# UKU100.net
KiCad netlist of a schematic drawn in Altium Designer
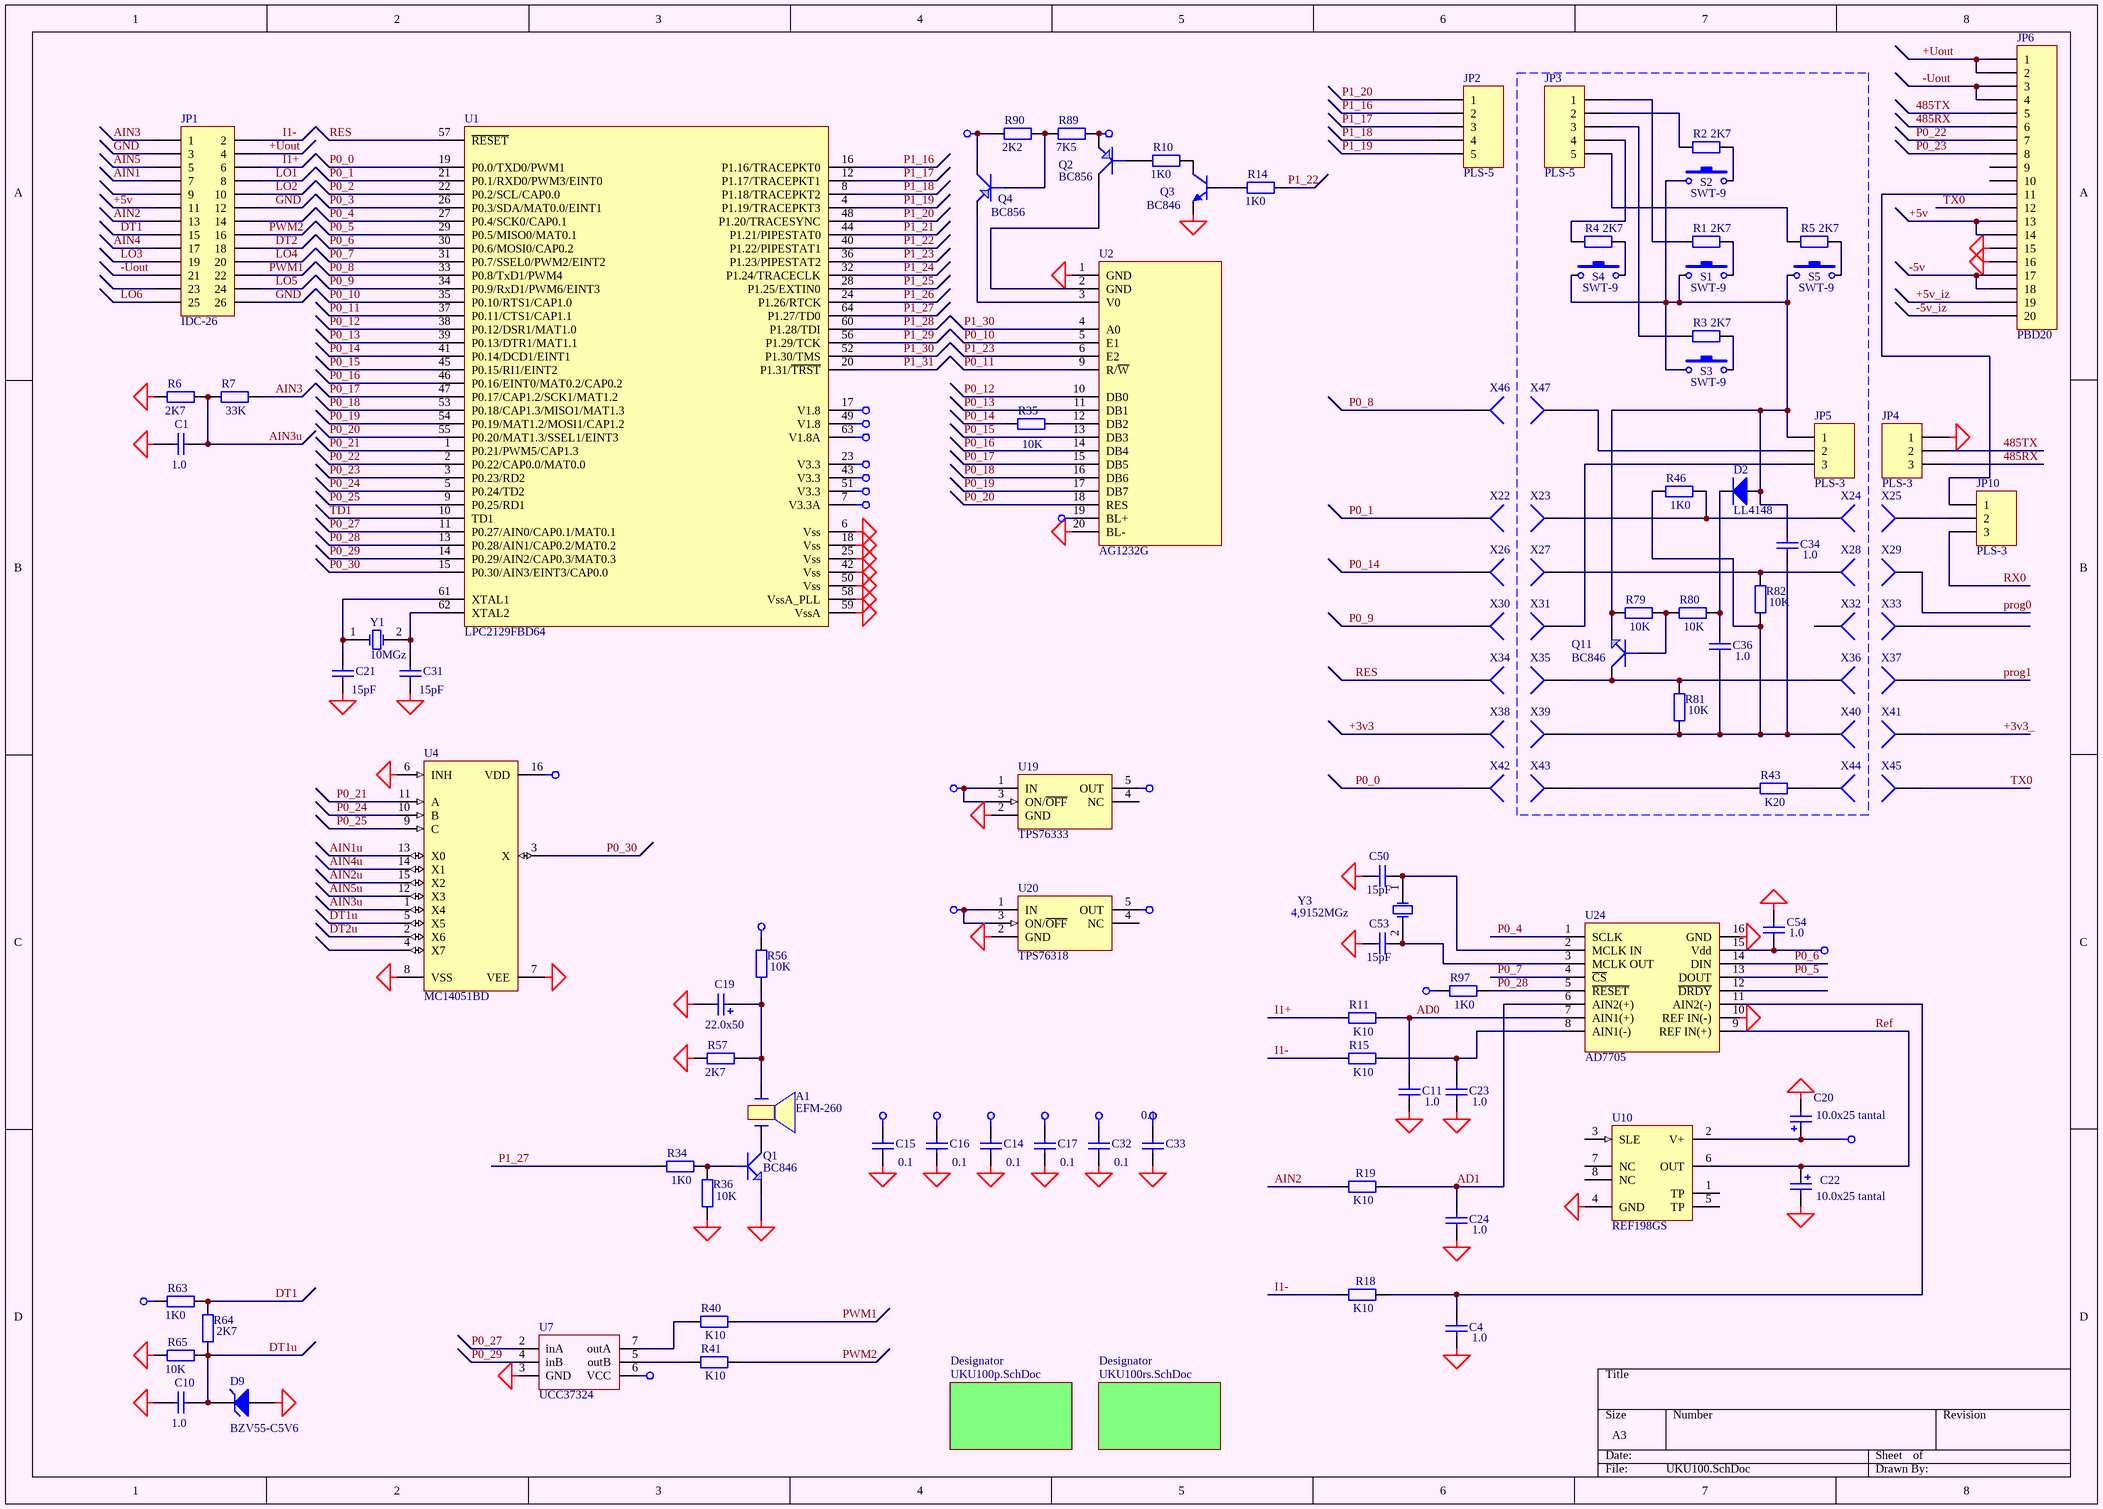
[diagram p0: UKU100.SchDoc]

(export (version "E")
  (design (tool "Eeschema 10.0.6"))
  (components
    (comp (ref "A1") (value "EFM-260") (footprint "Pjezo15") (libsource (lib "PAL") (part "PJEZ0")))
    (comp (ref "C1")
      (value "1.0")
      (footprint "C3216-1206")
      (description "Capacitor (Semiconductor SIM Model)")
      (fields (field (name "MANUFACTURER") "Generic Components") (field (name "PUBLISHER") "Altium Limited"))
      (libsource (lib "Miscellaneous Devices") (part "Cap Semi"))
    )
    (comp (ref "C4")
      (value "1.0")
      (footprint "_1206")
      (description "Capacitor (Semiconductor SIM Model)")
      (fields (field (name "MANUFACTURER") "Generic Components") (field (name "PUBLISHER") "Altium Limited"))
      (libsource (lib "Miscellaneous Devices") (part "Cap Semi"))
    )
    (comp (ref "C10")
      (value "1.0")
      (footprint "C3216-1206")
      (description "Capacitor (Semiconductor SIM Model)")
      (fields (field (name "MANUFACTURER") "Generic Components") (field (name "PUBLISHER") "Altium Limited"))
      (libsource (lib "Miscellaneous Devices") (part "Cap Semi"))
    )
    (comp (ref "C11")
      (value "1.0")
      (footprint "C3216-1206")
      (description "Capacitor (Semiconductor SIM Model)")
      (fields (field (name "MANUFACTURER") "Generic Components") (field (name "PUBLISHER") "Altium Limited"))
      (libsource (lib "Miscellaneous Devices") (part "Cap Semi"))
    )
    (comp (ref "C14")
      (value "0.1")
      (footprint "C3216-1206")
      (description "Capacitor (Semiconductor SIM Model)")
      (fields (field (name "MANUFACTURER") "Generic Components") (field (name "PUBLISHER") "Altium Limited"))
      (libsource (lib "Miscellaneous Devices") (part "Cap Semi"))
    )
    (comp (ref "C15")
      (value "0.1")
      (footprint "C3216-1206")
      (description "Capacitor (Semiconductor SIM Model)")
      (fields (field (name "MANUFACTURER") "Generic Components") (field (name "PUBLISHER") "Altium Limited"))
      (libsource (lib "Miscellaneous Devices") (part "Cap Semi"))
    )
    (comp (ref "C16")
      (value "0.1")
      (footprint "C3216-1206")
      (description "Capacitor (Semiconductor SIM Model)")
      (fields (field (name "MANUFACTURER") "Generic Components") (field (name "PUBLISHER") "Altium Limited"))
      (libsource (lib "Miscellaneous Devices") (part "Cap Semi"))
    )
    (comp (ref "C17")
      (value "0.1")
      (footprint "C3216-1206")
      (description "Capacitor (Semiconductor SIM Model)")
      (fields (field (name "MANUFACTURER") "Generic Components") (field (name "PUBLISHER") "Altium Limited"))
      (libsource (lib "Miscellaneous Devices") (part "Cap Semi"))
    )
    (comp (ref "C19")
      (value "22.0x50")
      (footprint "el3")
      (description "Polarized Capacitor (Radial)")
      (fields (field (name "MANUFACTURER") "Generic Components") (field (name "PUBLISHER") "Altium Limited"))
      (libsource (lib "PAL") (part "Cap Pol1"))
    )
    (comp (ref "C20")
      (value "10.0x25 tantal")
      (footprint "cap_el_6_3")
      (description "Polarized Capacitor (Surface Mount)")
      (fields (field (name "MANUFACTURER") "Generic Components") (field (name "PUBLISHER") "Altium Limited"))
      (libsource (lib "Miscellaneous Devices") (part "Cap Pol3"))
    )
    (comp (ref "C21")
      (value "15pF")
      (footprint "C3216-1206")
      (description "Capacitor (Semiconductor SIM Model)")
      (fields (field (name "MANUFACTURER") "Generic Components") (field (name "PUBLISHER") "Altium Limited"))
      (libsource (lib "Miscellaneous Devices") (part "Cap Semi"))
    )
    (comp (ref "C22")
      (value "10.0x25 tantal")
      (footprint "cap_el_6_3")
      (description "Polarized Capacitor (Surface Mount)")
      (fields (field (name "MANUFACTURER") "Generic Components") (field (name "PUBLISHER") "Altium Limited"))
      (libsource (lib "Miscellaneous Devices") (part "Cap Pol3"))
    )
    (comp (ref "C23")
      (value "1.0")
      (footprint "C3216-1206")
      (description "Capacitor (Semiconductor SIM Model)")
      (fields (field (name "MANUFACTURER") "Generic Components") (field (name "PUBLISHER") "Altium Limited"))
      (libsource (lib "Miscellaneous Devices") (part "Cap Semi"))
    )
    (comp (ref "C24")
      (value "1.0")
      (footprint "C3216-1206")
      (description "Capacitor (Semiconductor SIM Model)")
      (fields (field (name "MANUFACTURER") "Generic Components") (field (name "PUBLISHER") "Altium Limited"))
      (libsource (lib "Miscellaneous Devices") (part "Cap Semi"))
    )
    (comp (ref "C31")
      (value "15pF")
      (footprint "C3216-1206")
      (description "Capacitor (Semiconductor SIM Model)")
      (fields (field (name "MANUFACTURER") "Generic Components") (field (name "PUBLISHER") "Altium Limited"))
      (libsource (lib "Miscellaneous Devices") (part "Cap Semi"))
    )
    (comp (ref "C32")
      (value "0.1")
      (footprint "C3216-1206")
      (description "Capacitor (Semiconductor SIM Model)")
      (fields (field (name "MANUFACTURER") "Generic Components") (field (name "PUBLISHER") "Altium Limited"))
      (libsource (lib "Miscellaneous Devices") (part "Cap Semi"))
    )
    (comp (ref "C33")
      (value "0.1")
      (footprint "C3216-1206")
      (description "Capacitor (Semiconductor SIM Model)")
      (fields (field (name "MANUFACTURER") "Generic Components") (field (name "PUBLISHER") "Altium Limited"))
      (libsource (lib "Miscellaneous Devices") (part "Cap Semi"))
    )
    (comp (ref "C34")
      (value "1.0")
      (footprint "C3216-1206")
      (description "Capacitor (Semiconductor SIM Model)")
      (fields (field (name "MANUFACTURER") "Generic Components") (field (name "PUBLISHER") "Altium Limited"))
      (libsource (lib "Miscellaneous Devices") (part "Cap Semi"))
    )
    (comp (ref "C36")
      (value "1.0")
      (footprint "C3216-1206")
      (description "Capacitor (Semiconductor SIM Model)")
      (fields (field (name "MANUFACTURER") "Generic Components") (field (name "PUBLISHER") "Altium Limited"))
      (libsource (lib "Miscellaneous Devices") (part "Cap Semi"))
    )
    (comp (ref "C50")
      (value "15pF")
      (footprint "_1206")
      (description "Capacitor")
      (fields (field (name "MANUFACTURER") "Generic Components") (field (name "PUBLISHER") "Altium Limited"))
      (libsource (lib "") (part "Cap Semi_1"))
    )
    (comp (ref "C53")
      (value "15pF")
      (footprint "_1206")
      (description "Capacitor")
      (fields (field (name "MANUFACTURER") "Generic Components") (field (name "PUBLISHER") "Altium Limited"))
      (libsource (lib "") (part "Cap Semi_1"))
    )
    (comp (ref "C54")
      (value "1.0")
      (footprint "C3216-1206")
      (description "Capacitor")
      (fields (field (name "MANUFACTURER") "Generic Components") (field (name "PUBLISHER") "Altium Limited"))
      (libsource (lib "Miscellaneous Devices") (part "Cap Semi"))
    )
    (comp (ref "D2")
      (value "LL4148")
      (footprint "_1206d")
      (description "Default Diode")
      (fields (field (name "MANUFACTURER") "Generic Components") (field (name "PUBLISHER") "Altium Limited"))
      (libsource (lib "PAL") (part "Diode"))
    )
    (comp (ref "D9")
      (value "BZV55-C5V6")
      (footprint "_1206d")
      (description "Zener Diode")
      (fields (field (name "MANUFACTURER") "Generic Components") (field (name "PUBLISHER") "Altium Limited"))
      (libsource (lib "Miscellaneous Devices") (part "D Zener"))
    )
    (comp (ref "JP1")
      (value "IDC-26")
      (footprint "SCM-26")
      (description "Header, 13-Pin, Dual row")
      (fields (field (name "MANUFACTURER") "Generic Components") (field (name "PUBLISHER") "Altium Limited"))
      (libsource (lib "Miscellaneous Connectors") (part "MHDR2X13"))
    )
    (comp (ref "JP2")
      (value "PLS-5")
      (footprint "HDR1X5")
      (description "Header, 5-Pin")
      (fields (field (name "MANUFACTURER") "Generic Components") (field (name "PUBLISHER") "Altium Limited"))
      (libsource (lib "Miscellaneous Connectors") (part "Header 5"))
    )
    (comp (ref "JP3")
      (value "PLS-5")
      (footprint "HDR1X5")
      (description "Header, 5-Pin")
      (fields (field (name "MANUFACTURER") "Generic Components") (field (name "PUBLISHER") "Altium Limited"))
      (libsource (lib "") (part "Header 5_1"))
    )
    (comp (ref "JP4")
      (value "PLS-3")
      (footprint "HDR1X3")
      (description "Header, 3-Pin")
      (fields (field (name "MANUFACTURER") "Generic Components") (field (name "PUBLISHER") "Altium Limited"))
      (libsource (lib "") (part "Header 3_1"))
    )
    (comp (ref "JP5")
      (value "PLS-3")
      (footprint "HDR1X3")
      (description "Header, 3-Pin")
      (fields (field (name "MANUFACTURER") "Generic Components") (field (name "PUBLISHER") "Altium Limited"))
      (libsource (lib "Miscellaneous Connectors") (part "Header 3"))
    )
    (comp (ref "JP6")
      (value "PBD20")
      (footprint "HDR2X10")
      (description "Header, 20-Pin")
      (fields (field (name "MANUFACTURER") "Generic Components") (field (name "PUBLISHER") "Altium Limited"))
      (libsource (lib "Miscellaneous Connectors") (part "Header 20"))
    )
    (comp (ref "JP10")
      (value "PLS-3")
      (footprint "HDR1X3")
      (description "Header, 3-Pin")
      (fields (field (name "MANUFACTURER") "Generic Components") (field (name "PUBLISHER") "Altium Limited"))
      (libsource (lib "Miscellaneous Connectors") (part "Header 3"))
    )
    (comp (ref "Q1") (value "BC846") (footprint "SOT 23:SO-G3") (libsource (lib "MAIN") (part "GT122")))
    (comp (ref "Q2") (value "BC856") (footprint "SO-G3") (libsource (lib "MAIN") (part "GT109")))
    (comp (ref "Q3")
      (value "BC846")
      (footprint "SO-G3")
      (description "General Purpose Transistor NPN Silicon")
      (fields (field (name "MANUFACTURER") "Motorola") (field (name "PUBLISHER") "Altium Limited"))
      (libsource (lib "PAL") (part "BC847ALT1"))
    )
    (comp (ref "Q4") (value "BC856") (footprint "SO-G3") (libsource (lib "MAIN") (part "GT109")))
    (comp (ref "Q11") (value "BC846") (footprint "SOT 23:SO-G3") (libsource (lib "MAIN") (part "GT122")))
    (comp (ref "R1")
      (value "2K7")
      (footprint "_1206")
      (description "Resistor")
      (fields (field (name "MANUFACTURER") "Generic Components") (field (name "PUBLISHER") "Altium Limited"))
      (libsource (lib "") (part "Res2_3"))
    )
    (comp (ref "R2")
      (value "2K7")
      (footprint "_1206")
      (description "Resistor")
      (fields (field (name "MANUFACTURER") "Generic Components") (field (name "PUBLISHER") "Altium Limited"))
      (libsource (lib "") (part "Res2_3"))
    )
    (comp (ref "R3")
      (value "2K7")
      (footprint "_1206")
      (description "Resistor")
      (fields (field (name "MANUFACTURER") "Generic Components") (field (name "PUBLISHER") "Altium Limited"))
      (libsource (lib "") (part "Res2_3"))
    )
    (comp (ref "R4")
      (value "2K7")
      (footprint "_1206")
      (description "Resistor")
      (fields (field (name "MANUFACTURER") "Generic Components") (field (name "PUBLISHER") "Altium Limited"))
      (libsource (lib "") (part "Res2_3"))
    )
    (comp (ref "R5")
      (value "2K7")
      (footprint "_1206")
      (description "Resistor")
      (fields (field (name "MANUFACTURER") "Generic Components") (field (name "PUBLISHER") "Altium Limited"))
      (libsource (lib "") (part "Res2_3"))
    )
    (comp (ref "R6")
      (value "2K7")
      (footprint "_1206")
      (description "Resistor")
      (fields (field (name "MANUFACTURER") "Generic Components") (field (name "PUBLISHER") "Altium Limited"))
      (libsource (lib "") (part "Res2_1"))
    )
    (comp (ref "R7")
      (value "33K")
      (footprint "_1206")
      (description "Resistor")
      (fields (field (name "MANUFACTURER") "Generic Components") (field (name "PUBLISHER") "Altium Limited"))
      (libsource (lib "") (part "Res2_2"))
    )
    (comp (ref "R10")
      (value "1K0")
      (footprint "_1206")
      (description "Resistor")
      (fields (field (name "MANUFACTURER") "Generic Components") (field (name "PUBLISHER") "Altium Limited"))
      (libsource (lib "") (part "Res2_1"))
    )
    (comp (ref "R11")
      (value "K10")
      (footprint "_1206")
      (description "Resistor")
      (fields (field (name "MANUFACTURER") "Generic Components") (field (name "PUBLISHER") "Altium Limited"))
      (libsource (lib "") (part "Res2_1"))
    )
    (comp (ref "R14")
      (value "1K0")
      (footprint "_1206")
      (description "Resistor")
      (fields (field (name "MANUFACTURER") "Generic Components") (field (name "PUBLISHER") "Altium Limited"))
      (libsource (lib "") (part "Res2_1"))
    )
    (comp (ref "R15")
      (value "K10")
      (footprint "_1206")
      (description "Resistor")
      (fields (field (name "MANUFACTURER") "Generic Components") (field (name "PUBLISHER") "Altium Limited"))
      (libsource (lib "") (part "Res2_1"))
    )
    (comp (ref "R18")
      (value "K10")
      (footprint "_1206")
      (description "Resistor")
      (fields (field (name "MANUFACTURER") "Generic Components") (field (name "PUBLISHER") "Altium Limited"))
      (libsource (lib "") (part "Res2_1"))
    )
    (comp (ref "R19")
      (value "K10")
      (footprint "_1206")
      (description "Resistor")
      (fields (field (name "MANUFACTURER") "Generic Components") (field (name "PUBLISHER") "Altium Limited"))
      (libsource (lib "") (part "Res2_1"))
    )
    (comp (ref "R34")
      (value "1K0")
      (footprint "_1206")
      (description "Resistor")
      (fields (field (name "MANUFACTURER") "Generic Components") (field (name "PUBLISHER") "Altium Limited"))
      (libsource (lib "") (part "Res2_2"))
    )
    (comp (ref "R35")
      (value "10K")
      (footprint "_1206")
      (description "Resistor")
      (fields (field (name "MANUFACTURER") "Generic Components") (field (name "PUBLISHER") "Altium Limited"))
      (libsource (lib "") (part "Res2_2"))
    )
    (comp (ref "R36")
      (value "10K")
      (footprint "_1206")
      (description "Resistor")
      (fields (field (name "MANUFACTURER") "Generic Components") (field (name "PUBLISHER") "Altium Limited"))
      (libsource (lib "Miscellaneous Devices") (part "Res2"))
    )
    (comp (ref "R40")
      (value "K10")
      (footprint "_1206")
      (description "Resistor")
      (fields (field (name "MANUFACTURER") "Generic Components") (field (name "PUBLISHER") "Altium Limited"))
      (libsource (lib "") (part "Res2_1"))
    )
    (comp (ref "R41")
      (value "K10")
      (footprint "_1206")
      (description "Resistor")
      (fields (field (name "MANUFACTURER") "Generic Components") (field (name "PUBLISHER") "Altium Limited"))
      (libsource (lib "") (part "Res2_1"))
    )
    (comp (ref "R43")
      (value "K20")
      (footprint "_1206")
      (description "Resistor")
      (fields (field (name "MANUFACTURER") "Generic Components") (field (name "PUBLISHER") "Altium Limited"))
      (libsource (lib "") (part "Res2_2"))
    )
    (comp (ref "R46")
      (value "1K0")
      (footprint "_1206")
      (description "Resistor")
      (fields (field (name "MANUFACTURER") "Generic Components") (field (name "PUBLISHER") "Altium Limited"))
      (libsource (lib "") (part "Res2_1"))
    )
    (comp (ref "R56")
      (value "10K")
      (footprint "_1206")
      (description "Resistor")
      (fields (field (name "MANUFACTURER") "Generic Components") (field (name "PUBLISHER") "Altium Limited"))
      (libsource (lib "Miscellaneous Devices") (part "Res2"))
    )
    (comp (ref "R57")
      (value "2K7")
      (footprint "_1206")
      (description "Resistor")
      (fields (field (name "MANUFACTURER") "Generic Components") (field (name "PUBLISHER") "Altium Limited"))
      (libsource (lib "") (part "Res2_2"))
    )
    (comp (ref "R63")
      (value "1K0")
      (footprint "_1206")
      (description "Resistor")
      (fields (field (name "MANUFACTURER") "Generic Components") (field (name "PUBLISHER") "Altium Limited"))
      (libsource (lib "") (part "Res2_1"))
    )
    (comp (ref "R64")
      (value "2K7")
      (footprint "_1206")
      (description "Resistor")
      (fields (field (name "MANUFACTURER") "Generic Components") (field (name "PUBLISHER") "Altium Limited"))
      (libsource (lib "") (part "Res2_3"))
    )
    (comp (ref "R65")
      (value "10K")
      (footprint "_1206")
      (description "Resistor")
      (fields (field (name "MANUFACTURER") "Generic Components") (field (name "PUBLISHER") "Altium Limited"))
      (libsource (lib "") (part "Res2_2"))
    )
    (comp (ref "R79")
      (value "10K")
      (footprint "_1206")
      (description "Resistor")
      (fields (field (name "MANUFACTURER") "Generic Components") (field (name "PUBLISHER") "Altium Limited"))
      (libsource (lib "") (part "Res2_2"))
    )
    (comp (ref "R80")
      (value "10K")
      (footprint "_1206")
      (description "Resistor")
      (fields (field (name "MANUFACTURER") "Generic Components") (field (name "PUBLISHER") "Altium Limited"))
      (libsource (lib "") (part "Res2_2"))
    )
    (comp (ref "R81")
      (value "10K")
      (footprint "_1206")
      (description "Resistor")
      (fields (field (name "MANUFACTURER") "Generic Components") (field (name "PUBLISHER") "Altium Limited"))
      (libsource (lib "Miscellaneous Devices") (part "Res2"))
    )
    (comp (ref "R82")
      (value "10K")
      (footprint "_1206")
      (description "Resistor")
      (fields (field (name "MANUFACTURER") "Generic Components") (field (name "PUBLISHER") "Altium Limited"))
      (libsource (lib "Miscellaneous Devices") (part "Res2"))
    )
    (comp (ref "R89")
      (value "7K5")
      (footprint "_1206")
      (description "Resistor")
      (fields (field (name "MANUFACTURER") "Generic Components") (field (name "PUBLISHER") "Altium Limited"))
      (libsource (lib "") (part "Res2_2"))
    )
    (comp (ref "R90")
      (value "2K2")
      (footprint "_1206")
      (description "Resistor")
      (fields (field (name "MANUFACTURER") "Generic Components") (field (name "PUBLISHER") "Altium Limited"))
      (libsource (lib "") (part "Res2_2"))
    )
    (comp (ref "R97")
      (value "1K0")
      (footprint "_1206")
      (description "Resistor")
      (fields (field (name "MANUFACTURER") "Generic Components") (field (name "PUBLISHER") "Altium Limited"))
      (libsource (lib "") (part "Res2_1"))
    )
    (comp (ref "S1")
      (value "SWT-9")
      (footprint "SWT-9")
      (description "Switch")
      (fields (field (name "MANUFACTURER") "Generic Components") (field (name "PUBLISHER") "Altium Limited"))
      (libsource (lib "PAL") (part "SWT-9"))
    )
    (comp (ref "S2")
      (value "SWT-9")
      (footprint "SWT-9")
      (description "Switch")
      (fields (field (name "MANUFACTURER") "Generic Components") (field (name "PUBLISHER") "Altium Limited"))
      (libsource (lib "PAL") (part "SWT-9"))
    )
    (comp (ref "S3")
      (value "SWT-9")
      (footprint "SWT-9")
      (description "Switch")
      (fields (field (name "MANUFACTURER") "Generic Components") (field (name "PUBLISHER") "Altium Limited"))
      (libsource (lib "PAL") (part "SWT-9"))
    )
    (comp (ref "S4")
      (value "SWT-9")
      (footprint "SWT-9")
      (description "Switch")
      (fields (field (name "MANUFACTURER") "Generic Components") (field (name "PUBLISHER") "Altium Limited"))
      (libsource (lib "PAL") (part "SWT-9"))
    )
    (comp (ref "S5")
      (value "SWT-9")
      (footprint "SWT-9")
      (description "Switch")
      (fields (field (name "MANUFACTURER") "Generic Components") (field (name "PUBLISHER") "Altium Limited"))
      (libsource (lib "PAL") (part "SWT-9"))
    )
    (comp (ref "U1")
      (value "LPC2129FBD64")
      (footprint "F-QFP10X10-G64/P.5N")
      (libsource (lib "PAL") (part "LPC2129FBD64"))
    )
    (comp (ref "U2") (value "AG1232G") (footprint "AG1232G") (libsource (lib "PAL") (part "AG1232G")))
    (comp (ref "U4")
      (value "MC14051BD")
      (footprint "SO-G16/C5.85")
      (description "8-Channel Analog Multiplexer/Demultiplexer")
      (fields (field (name "MANUFACTURER") "ON Semiconductor") (field (name "PUBLISHER") "Altium Limited"))
      (libsource (lib "ON Semi Logic Multiplexer") (part "MC14051BD"))
    )
    (comp (ref "U7") (value "UCC37324") (footprint "SO-G8") (libsource (lib "PAL") (part "UCC37324")))
    (comp (ref "U10")
      (value "REF198GS")
      (footprint "SO-G8")
      (description "Precision Micropower, Low-Dropout, Voltage Reference")
      (fields (field (name "MANUFACTURER") "Analog Devices") (field (name "PUBLISHER") "Altium Limited"))
      (libsource (lib "AD Power Mgt Voltage Reference") (part "REF198GS"))
    )
    (comp (ref "U19")
      (value "TPS76333")
      (footprint "SO-G5/P.95")
      (description "Micropower SOT, 50 mA Ultra Low-Dropout Regulator")
      (fields
        (field (name "MANUFACTURER") "National Semiconductor")
        (field (name "PUBLISHER") "Altium Limited")
      )
      (libsource (lib "NSC Power Mgt Voltage Regulator") (part "LP2980AIM5-3.3"))
    )
    (comp (ref "U20")
      (value "TPS76318")
      (footprint "SO-G5/P.95")
      (description "Micropower SOT, 50 mA Ultra Low-Dropout Regulator")
      (fields
        (field (name "MANUFACTURER") "National Semiconductor")
        (field (name "PUBLISHER") "Altium Limited")
      )
      (libsource (lib "NSC Power Mgt Voltage Regulator") (part "LP2980AIM5-3.3"))
    )
    (comp (ref "U24")
      (value "AD7705")
      (footprint "SO-G16/D10.4")
      (description "ADC")
      (libsource (lib "PAL") (part "AD7705"))
    )
    (comp (ref "X22")
      (value "~")
      (footprint "PIN1")
      (description "Socket")
      (fields (field (name "MANUFACTURER") "Generic Components") (field (name "PUBLISHER") "Altium Limited"))
      (libsource (lib "Miscellaneous Connectors") (part "Socket"))
    )
    (comp (ref "X23")
      (value "~")
      (footprint "PIN1")
      (description "Socket")
      (fields (field (name "MANUFACTURER") "Generic Components") (field (name "PUBLISHER") "Altium Limited"))
      (libsource (lib "Miscellaneous Connectors") (part "Socket"))
    )
    (comp (ref "X24")
      (value "~")
      (footprint "PIN1")
      (description "Socket")
      (fields (field (name "MANUFACTURER") "Generic Components") (field (name "PUBLISHER") "Altium Limited"))
      (libsource (lib "Miscellaneous Connectors") (part "Socket"))
    )
    (comp (ref "X25")
      (value "~")
      (footprint "PIN1")
      (description "Socket")
      (fields (field (name "MANUFACTURER") "Generic Components") (field (name "PUBLISHER") "Altium Limited"))
      (libsource (lib "Miscellaneous Connectors") (part "Socket"))
    )
    (comp (ref "X26")
      (value "~")
      (footprint "PIN1")
      (description "Socket")
      (fields (field (name "MANUFACTURER") "Generic Components") (field (name "PUBLISHER") "Altium Limited"))
      (libsource (lib "Miscellaneous Connectors") (part "Socket"))
    )
    (comp (ref "X27")
      (value "~")
      (footprint "PIN1")
      (description "Socket")
      (fields (field (name "MANUFACTURER") "Generic Components") (field (name "PUBLISHER") "Altium Limited"))
      (libsource (lib "Miscellaneous Connectors") (part "Socket"))
    )
    (comp (ref "X28")
      (value "~")
      (footprint "PIN1")
      (description "Socket")
      (fields (field (name "MANUFACTURER") "Generic Components") (field (name "PUBLISHER") "Altium Limited"))
      (libsource (lib "Miscellaneous Connectors") (part "Socket"))
    )
    (comp (ref "X29")
      (value "~")
      (footprint "PIN1")
      (description "Socket")
      (fields (field (name "MANUFACTURER") "Generic Components") (field (name "PUBLISHER") "Altium Limited"))
      (libsource (lib "Miscellaneous Connectors") (part "Socket"))
    )
    (comp (ref "X30")
      (value "~")
      (footprint "PIN1")
      (description "Socket")
      (fields (field (name "MANUFACTURER") "Generic Components") (field (name "PUBLISHER") "Altium Limited"))
      (libsource (lib "Miscellaneous Connectors") (part "Socket"))
    )
    (comp (ref "X31")
      (value "~")
      (footprint "PIN1")
      (description "Socket")
      (fields (field (name "MANUFACTURER") "Generic Components") (field (name "PUBLISHER") "Altium Limited"))
      (libsource (lib "Miscellaneous Connectors") (part "Socket"))
    )
    (comp (ref "X32")
      (value "~")
      (footprint "PIN1")
      (description "Socket")
      (fields (field (name "MANUFACTURER") "Generic Components") (field (name "PUBLISHER") "Altium Limited"))
      (libsource (lib "Miscellaneous Connectors") (part "Socket"))
    )
    (comp (ref "X33")
      (value "~")
      (footprint "PIN1")
      (description "Socket")
      (fields (field (name "MANUFACTURER") "Generic Components") (field (name "PUBLISHER") "Altium Limited"))
      (libsource (lib "Miscellaneous Connectors") (part "Socket"))
    )
    (comp (ref "X34")
      (value "~")
      (footprint "PIN1")
      (description "Socket")
      (fields (field (name "MANUFACTURER") "Generic Components") (field (name "PUBLISHER") "Altium Limited"))
      (libsource (lib "Miscellaneous Connectors") (part "Socket"))
    )
    (comp (ref "X35")
      (value "~")
      (footprint "PIN1")
      (description "Socket")
      (fields (field (name "MANUFACTURER") "Generic Components") (field (name "PUBLISHER") "Altium Limited"))
      (libsource (lib "Miscellaneous Connectors") (part "Socket"))
    )
    (comp (ref "X36")
      (value "~")
      (footprint "PIN1")
      (description "Socket")
      (fields (field (name "MANUFACTURER") "Generic Components") (field (name "PUBLISHER") "Altium Limited"))
      (libsource (lib "Miscellaneous Connectors") (part "Socket"))
    )
    (comp (ref "X37")
      (value "~")
      (footprint "PIN1")
      (description "Socket")
      (fields (field (name "MANUFACTURER") "Generic Components") (field (name "PUBLISHER") "Altium Limited"))
      (libsource (lib "Miscellaneous Connectors") (part "Socket"))
    )
    (comp (ref "X38")
      (value "~")
      (footprint "PIN1")
      (description "Socket")
      (fields (field (name "MANUFACTURER") "Generic Components") (field (name "PUBLISHER") "Altium Limited"))
      (libsource (lib "Miscellaneous Connectors") (part "Socket"))
    )
    (comp (ref "X39")
      (value "~")
      (footprint "PIN1")
      (description "Socket")
      (fields (field (name "MANUFACTURER") "Generic Components") (field (name "PUBLISHER") "Altium Limited"))
      (libsource (lib "Miscellaneous Connectors") (part "Socket"))
    )
    (comp (ref "X40")
      (value "~")
      (footprint "PIN1")
      (description "Socket")
      (fields (field (name "MANUFACTURER") "Generic Components") (field (name "PUBLISHER") "Altium Limited"))
      (libsource (lib "Miscellaneous Connectors") (part "Socket"))
    )
    (comp (ref "X41")
      (value "~")
      (footprint "PIN1")
      (description "Socket")
      (fields (field (name "MANUFACTURER") "Generic Components") (field (name "PUBLISHER") "Altium Limited"))
      (libsource (lib "Miscellaneous Connectors") (part "Socket"))
    )
    (comp (ref "X42")
      (value "~")
      (footprint "PIN1")
      (description "Socket")
      (fields (field (name "MANUFACTURER") "Generic Components") (field (name "PUBLISHER") "Altium Limited"))
      (libsource (lib "Miscellaneous Connectors") (part "Socket"))
    )
    (comp (ref "X43")
      (value "~")
      (footprint "PIN1")
      (description "Socket")
      (fields (field (name "MANUFACTURER") "Generic Components") (field (name "PUBLISHER") "Altium Limited"))
      (libsource (lib "Miscellaneous Connectors") (part "Socket"))
    )
    (comp (ref "X44")
      (value "~")
      (footprint "PIN1")
      (description "Socket")
      (fields (field (name "MANUFACTURER") "Generic Components") (field (name "PUBLISHER") "Altium Limited"))
      (libsource (lib "Miscellaneous Connectors") (part "Socket"))
    )
    (comp (ref "X45")
      (value "~")
      (footprint "PIN1")
      (description "Socket")
      (fields (field (name "MANUFACTURER") "Generic Components") (field (name "PUBLISHER") "Altium Limited"))
      (libsource (lib "Miscellaneous Connectors") (part "Socket"))
    )
    (comp (ref "X46")
      (value "~")
      (footprint "PIN1")
      (description "Socket")
      (fields (field (name "MANUFACTURER") "Generic Components") (field (name "PUBLISHER") "Altium Limited"))
      (libsource (lib "Miscellaneous Connectors") (part "Socket"))
    )
    (comp (ref "X47")
      (value "~")
      (footprint "PIN1")
      (description "Socket")
      (fields (field (name "MANUFACTURER") "Generic Components") (field (name "PUBLISHER") "Altium Limited"))
      (libsource (lib "Miscellaneous Connectors") (part "Socket"))
    )
    (comp (ref "Y1")
      (value "10MGz")
      (footprint "QWARZ1")
      (description "Crystal Oscillator")
      (fields (field (name "MANUFACTURER") "Generic Components") (field (name "PUBLISHER") "Altium Limited"))
      (libsource (lib "") (part "XTAL_1"))
    )
    (comp (ref "Y3")
      (value "4,9152MGz")
      (footprint "QWARZ1")
      (description "Crystal Oscillator")
      (fields (field (name "MANUFACTURER") "Generic Components") (field (name "PUBLISHER") "Altium Limited"))
      (libsource (lib "Miscellaneous Devices") (part "XTAL"))
    )
  )
  (nets
    (net (code "1") (name "+1v8") (class "Default")
      (node (ref "C14") (pin "2") (pinfunction "2_2") (pintype "passive"))
      (node (ref "C32") (pin "2") (pinfunction "2_2") (pintype "passive"))
      (node (ref "U1") (pin "17") (pinfunction "V1.8_17") (pintype "passive"))
      (node (ref "U1") (pin "49") (pinfunction "V1.8_49") (pintype "passive"))
      (node (ref "U1") (pin "63") (pinfunction "V1.8A_63") (pintype "passive"))
      (node (ref "U20") (pin "5") (pinfunction "OUT_5") (pintype "power_in"))
    )
    (net (code "2") (name "+3v3") (class "Default")
      (node (ref "C33") (pin "2") (pinfunction "2_2") (pintype "passive"))
      (node (ref "U1") (pin "23") (pinfunction "V3.3_23") (pintype "passive"))
      (node (ref "U1") (pin "43") (pinfunction "V3.3_43") (pintype "passive"))
      (node (ref "U1") (pin "51") (pinfunction "V3.3_51") (pintype "passive"))
      (node (ref "U1") (pin "7") (pinfunction "V3.3A_7") (pintype "passive"))
      (node (ref "X38") (pin "1") (pinfunction "1_1") (pintype "passive"))
    )
    (net (code "3") (name "+3v3_") (class "Default")
      (node (ref "C17") (pin "2") (pinfunction "2_2") (pintype "passive"))
      (node (ref "U19") (pin "5") (pinfunction "OUT_5") (pintype "power_in"))
      (node (ref "X41") (pin "1") (pinfunction "1_1") (pintype "passive"))
    )
    (net (code "4") (name "+5v") (class "Default")
      (node (ref "C15") (pin "2") (pinfunction "2_2") (pintype "passive"))
      (node (ref "C20") (pin "1") (pinfunction "1_1") (pintype "passive"))
      (node (ref "C54") (pin "2") (pinfunction "2_2") (pintype "passive"))
      (node (ref "JP1") (pin "11") (pinfunction "11_11") (pintype "passive"))
      (node (ref "JP6") (pin "13") (pinfunction "13_13") (pintype "passive"))
      (node (ref "JP6") (pin "14") (pinfunction "14_14") (pintype "passive"))
      (node (ref "Q2") (pin "2") (pinfunction "E_2") (pintype "passive"))
      (node (ref "R63") (pin "2") (pinfunction "2_2") (pintype "passive"))
      (node (ref "R89") (pin "2") (pinfunction "2_2") (pintype "passive"))
      (node (ref "R97") (pin "2") (pinfunction "2_2") (pintype "passive"))
      (node (ref "U10") (pin "2") (pinfunction "V+_2") (pintype "power_in"))
      (node (ref "U19") (pin "1") (pinfunction "IN_1") (pintype "power_in"))
      (node (ref "U19") (pin "3") (pinfunction "ON/~{OFF}_3") (pintype "input"))
      (node (ref "U2") (pin "19") (pinfunction "BL+_19") (pintype "passive"))
      (node (ref "U20") (pin "1") (pinfunction "IN_1") (pintype "power_in"))
      (node (ref "U20") (pin "3") (pinfunction "ON/~{OFF}_3") (pintype "input"))
      (node (ref "U24") (pin "15") (pinfunction "Vdd_15") (pintype "passive"))
      (node (ref "U4") (pin "16") (pinfunction "VDD_16") (pintype "power_in"))
      (node (ref "U7") (pin "6") (pinfunction "VCC_6") (pintype "passive"))
    )
    (net (code "5") (name "+Uout") (class "Default")
      (node (ref "JP1") (pin "4") (pinfunction "4_4") (pintype "passive"))
      (node (ref "JP6") (pin "1") (pinfunction "1_1") (pintype "passive"))
      (node (ref "JP6") (pin "2") (pinfunction "2_2") (pintype "passive"))
      (node (ref "R56") (pin "2") (pinfunction "2_2") (pintype "passive"))
    )
    (net (code "6") (name "-5v") (class "Default")
      (node (ref "C16") (pin "2") (pinfunction "2_2") (pintype "passive"))
      (node (ref "JP6") (pin "17") (pinfunction "17_17") (pintype "passive"))
      (node (ref "JP6") (pin "18") (pinfunction "18_18") (pintype "passive"))
      (node (ref "Q4") (pin "3") (pinfunction "C_3") (pintype "passive"))
      (node (ref "R90") (pin "1") (pinfunction "1_1") (pintype "passive"))
    )
    (net (code "7") (name "/+5v_iz") (class "Default")
      (node (ref "JP6") (pin "19") (pinfunction "19_19") (pintype "passive"))
    )
    (net (code "8") (name "/-5v_iz") (class "Default")
      (node (ref "JP6") (pin "20") (pinfunction "20_20") (pintype "passive"))
    )
    (net (code "9") (name "/-Uout") (class "Default")
      (node (ref "JP1") (pin "21") (pinfunction "21_21") (pintype "passive"))
      (node (ref "JP6") (pin "3") (pinfunction "3_3") (pintype "passive"))
      (node (ref "JP6") (pin "4") (pinfunction "4_4") (pintype "passive"))
    )
    (net (code "10") (name "/485RX") (class "Default")
      (node (ref "JP4") (pin "3") (pinfunction "3_3") (pintype "passive"))
      (node (ref "JP6") (pin "6") (pinfunction "6_6") (pintype "passive"))
    )
    (net (code "11") (name "/485TX") (class "Default")
      (node (ref "JP4") (pin "2") (pinfunction "2_2") (pintype "passive"))
      (node (ref "JP6") (pin "5") (pinfunction "5_5") (pintype "passive"))
    )
    (net (code "12") (name "/AD0") (class "Default")
      (node (ref "C11") (pin "2") (pinfunction "2_2") (pintype "passive"))
      (node (ref "R11") (pin "1") (pinfunction "1_1") (pintype "passive"))
      (node (ref "U24") (pin "7") (pinfunction "AIN1(+)_7") (pintype "passive"))
    )
    (net (code "13") (name "/AD1") (class "Default")
      (node (ref "C24") (pin "2") (pinfunction "2_2") (pintype "passive"))
      (node (ref "R19") (pin "1") (pinfunction "1_1") (pintype "passive"))
      (node (ref "U24") (pin "6") (pinfunction "AIN2(+)_6") (pintype "passive"))
    )
    (net (code "14") (name "/AIN1") (class "Default")
      (node (ref "JP1") (pin "7") (pinfunction "7_7") (pintype "passive"))
    )
    (net (code "15") (name "/AIN1u") (class "Default")
      (node (ref "U4") (pin "13") (pinfunction "X0_13") (pintype "bidirectional"))
    )
    (net (code "16") (name "/AIN2") (class "Default")
      (node (ref "JP1") (pin "13") (pinfunction "13_13") (pintype "passive"))
      (node (ref "R19") (pin "2") (pinfunction "2_2") (pintype "passive"))
    )
    (net (code "17") (name "/AIN2u") (class "Default")
      (node (ref "U4") (pin "15") (pinfunction "X2_15") (pintype "bidirectional"))
    )
    (net (code "18") (name "/AIN3") (class "Default")
      (node (ref "JP1") (pin "1") (pinfunction "1_1") (pintype "passive"))
      (node (ref "R7") (pin "2") (pinfunction "2_2") (pintype "passive"))
    )
    (net (code "19") (name "/AIN3u") (class "Default")
      (node (ref "C1") (pin "1") (pinfunction "1_1") (pintype "passive"))
      (node (ref "R6") (pin "1") (pinfunction "1_1") (pintype "passive"))
      (node (ref "R7") (pin "1") (pinfunction "1_1") (pintype "passive"))
      (node (ref "U4") (pin "1") (pinfunction "X4_1") (pintype "bidirectional"))
    )
    (net (code "20") (name "/AIN4") (class "Default")
      (node (ref "JP1") (pin "17") (pinfunction "17_17") (pintype "passive"))
    )
    (net (code "21") (name "/AIN4u") (class "Default")
      (node (ref "U4") (pin "14") (pinfunction "X1_14") (pintype "bidirectional"))
    )
    (net (code "22") (name "/AIN5") (class "Default")
      (node (ref "JP1") (pin "5") (pinfunction "5_5") (pintype "passive"))
    )
    (net (code "23") (name "/AIN5u") (class "Default")
      (node (ref "U4") (pin "12") (pinfunction "X3_12") (pintype "bidirectional"))
    )
    (net (code "24") (name "/DT1") (class "Default")
      (node (ref "JP1") (pin "15") (pinfunction "15_15") (pintype "passive"))
      (node (ref "R63") (pin "1") (pinfunction "1_1") (pintype "passive"))
      (node (ref "R64") (pin "1") (pinfunction "1_1") (pintype "passive"))
    )
    (net (code "25") (name "/DT1u") (class "Default")
      (node (ref "C10") (pin "1") (pinfunction "1_1") (pintype "passive"))
      (node (ref "D9") (pin "2") (pinfunction "K_2") (pintype "passive"))
      (node (ref "R64") (pin "2") (pinfunction "2_2") (pintype "passive"))
      (node (ref "R65") (pin "2") (pinfunction "2_2") (pintype "passive"))
      (node (ref "U4") (pin "5") (pinfunction "X5_5") (pintype "bidirectional"))
    )
    (net (code "26") (name "/DT2") (class "Default")
      (node (ref "JP1") (pin "18") (pinfunction "18_18") (pintype "passive"))
    )
    (net (code "27") (name "/DT2u") (class "Default")
      (node (ref "U4") (pin "2") (pinfunction "X6_2") (pintype "bidirectional"))
    )
    (net (code "28") (name "/I1+") (class "Default")
      (node (ref "JP1") (pin "6") (pinfunction "6_6") (pintype "passive"))
      (node (ref "R11") (pin "2") (pinfunction "2_2") (pintype "passive"))
    )
    (net (code "29") (name "/I1-") (class "Default")
      (node (ref "JP1") (pin "2") (pinfunction "2_2") (pintype "passive"))
      (node (ref "R15") (pin "2") (pinfunction "2_2") (pintype "passive"))
      (node (ref "R18") (pin "2") (pinfunction "2_2") (pintype "passive"))
    )
    (net (code "30") (name "/LO1") (class "Default")
      (node (ref "JP1") (pin "8") (pinfunction "8_8") (pintype "passive"))
    )
    (net (code "31") (name "/LO2") (class "Default")
      (node (ref "JP1") (pin "10") (pinfunction "10_10") (pintype "passive"))
    )
    (net (code "32") (name "/LO3") (class "Default")
      (node (ref "JP1") (pin "19") (pinfunction "19_19") (pintype "passive"))
    )
    (net (code "33") (name "/LO4") (class "Default")
      (node (ref "JP1") (pin "20") (pinfunction "20_20") (pintype "passive"))
    )
    (net (code "34") (name "/LO5") (class "Default")
      (node (ref "JP1") (pin "24") (pinfunction "24_24") (pintype "passive"))
    )
    (net (code "35") (name "/LO6") (class "Default")
      (node (ref "JP1") (pin "25") (pinfunction "25_25") (pintype "passive"))
    )
    (net (code "36") (name "/P0_0") (class "Default")
      (node (ref "U1") (pin "19") (pinfunction "P0.0/TXD0/PWM1_19") (pintype "passive"))
      (node (ref "X42") (pin "1") (pinfunction "1_1") (pintype "passive"))
    )
    (net (code "37") (name "/P0_1") (class "Default")
      (node (ref "U1") (pin "21") (pinfunction "P0.1/RXD0/PWM3/EINT0_21") (pintype "passive"))
      (node (ref "X22") (pin "1") (pinfunction "1_1") (pintype "passive"))
    )
    (net (code "38") (name "/P0_2") (class "Default")
      (node (ref "U1") (pin "22") (pinfunction "P0.2/SCL/CAP0.0_22") (pintype "passive"))
    )
    (net (code "39") (name "/P0_3") (class "Default")
      (node (ref "U1") (pin "26") (pinfunction "P0.3/SDA/MAT0.0/EINT1_26") (pintype "passive"))
    )
    (net (code "40") (name "/P0_4") (class "Default")
      (node (ref "U1") (pin "27") (pinfunction "P0.4/SCK0/CAP0.1_27") (pintype "passive"))
      (node (ref "U24") (pin "1") (pinfunction "SCLK_1") (pintype "passive"))
    )
    (net (code "41") (name "/P0_5") (class "Default")
      (node (ref "U1") (pin "29") (pinfunction "P0.5/MISO0/MAT0.1_29") (pintype "passive"))
      (node (ref "U24") (pin "13") (pinfunction "DOUT_13") (pintype "passive"))
    )
    (net (code "42") (name "/P0_6") (class "Default")
      (node (ref "U1") (pin "30") (pinfunction "P0.6/MOSI0/CAP0.2_30") (pintype "passive"))
      (node (ref "U24") (pin "14") (pinfunction "DIN_14") (pintype "passive"))
    )
    (net (code "43") (name "/P0_7") (class "Default")
      (node (ref "U1") (pin "31") (pinfunction "P0.7/SSEL0/PWM2/EINT2_31") (pintype "passive"))
      (node (ref "U24") (pin "4") (pinfunction "~{CS}_4") (pintype "passive"))
    )
    (net (code "44") (name "/P0_8") (class "Default")
      (node (ref "U1") (pin "33") (pinfunction "P0.8/TxD1/PWM4_33") (pintype "passive"))
      (node (ref "X46") (pin "1") (pinfunction "1_1") (pintype "passive"))
    )
    (net (code "45") (name "/P0_9") (class "Default")
      (node (ref "U1") (pin "34") (pinfunction "P0.9/RxD1/PWM6/EINT3_34") (pintype "passive"))
      (node (ref "X30") (pin "1") (pinfunction "1_1") (pintype "passive"))
    )
    (net (code "46") (name "/P0_10") (class "Default")
      (node (ref "U1") (pin "35") (pinfunction "P0.10/RTS1/CAP1.0_35") (pintype "passive"))
      (node (ref "U2") (pin "5") (pinfunction "E1_5") (pintype "passive"))
    )
    (net (code "47") (name "/P0_11") (class "Default")
      (node (ref "U1") (pin "37") (pinfunction "P0.11/CTS1/CAP1.1_37") (pintype "passive"))
      (node (ref "U2") (pin "9") (pinfunction "R/~{W}_9") (pintype "passive"))
    )
    (net (code "48") (name "/P0_12") (class "Default")
      (node (ref "U1") (pin "38") (pinfunction "P0.12/DSR1/MAT1.0_38") (pintype "passive"))
      (node (ref "U2") (pin "10") (pinfunction "DB0_10") (pintype "passive"))
    )
    (net (code "49") (name "/P0_13") (class "Default")
      (node (ref "U1") (pin "39") (pinfunction "P0.13/DTR1/MAT1.1_39") (pintype "passive"))
      (node (ref "U2") (pin "11") (pinfunction "DB1_11") (pintype "passive"))
    )
    (net (code "50") (name "/P0_14") (class "Default")
      (node (ref "R35") (pin "1") (pinfunction "1_1") (pintype "passive"))
      (node (ref "U1") (pin "41") (pinfunction "P0.14/DCD1/EINT1_41") (pintype "passive"))
      (node (ref "X26") (pin "1") (pinfunction "1_1") (pintype "passive"))
    )
    (net (code "51") (name "/P0_15") (class "Default")
      (node (ref "U1") (pin "45") (pinfunction "P0.15/RI1/EINT2_45") (pintype "passive"))
      (node (ref "U2") (pin "13") (pinfunction "DB3_13") (pintype "passive"))
    )
    (net (code "52") (name "/P0_16") (class "Default")
      (node (ref "U1") (pin "46") (pinfunction "P0.16/EINT0/MAT0.2/CAP0.2_46") (pintype "passive"))
      (node (ref "U2") (pin "14") (pinfunction "DB4_14") (pintype "passive"))
    )
    (net (code "53") (name "/P0_17") (class "Default")
      (node (ref "U1") (pin "47") (pinfunction "P0.17/CAP1.2/SCK1/MAT1.2_47") (pintype "passive"))
      (node (ref "U2") (pin "15") (pinfunction "DB5_15") (pintype "passive"))
    )
    (net (code "54") (name "/P0_18") (class "Default")
      (node (ref "U1") (pin "53") (pinfunction "P0.18/CAP1.3/MISO1/MAT1.3_53") (pintype "passive"))
      (node (ref "U2") (pin "16") (pinfunction "DB6_16") (pintype "passive"))
    )
    (net (code "55") (name "/P0_19") (class "Default")
      (node (ref "U1") (pin "54") (pinfunction "P0.19/MAT1.2/MOSI1/CAP1.2_54") (pintype "passive"))
      (node (ref "U2") (pin "17") (pinfunction "DB7_17") (pintype "passive"))
    )
    (net (code "56") (name "/P0_20") (class "Default")
      (node (ref "U1") (pin "55") (pinfunction "P0.20/MAT1.3/SSEL1/EINT3_55") (pintype "passive"))
      (node (ref "U2") (pin "18") (pinfunction "RES_18") (pintype "passive"))
    )
    (net (code "57") (name "/P0_21") (class "Default")
      (node (ref "U1") (pin "1") (pinfunction "P0.21/PWM5/CAP1.3_1") (pintype "passive"))
      (node (ref "U4") (pin "11") (pinfunction "A_11") (pintype "input"))
    )
    (net (code "58") (name "/P0_22") (class "Default")
      (node (ref "JP6") (pin "7") (pinfunction "7_7") (pintype "passive"))
      (node (ref "U1") (pin "2") (pinfunction "P0.22/CAP0.0/MAT0.0_2") (pintype "passive"))
    )
    (net (code "59") (name "/P0_23") (class "Default")
      (node (ref "JP6") (pin "8") (pinfunction "8_8") (pintype "passive"))
      (node (ref "U1") (pin "3") (pinfunction "P0.23/RD2_3") (pintype "passive"))
    )
    (net (code "60") (name "/P0_24") (class "Default")
      (node (ref "U1") (pin "5") (pinfunction "P0.24/TD2_5") (pintype "passive"))
      (node (ref "U4") (pin "10") (pinfunction "B_10") (pintype "input"))
    )
    (net (code "61") (name "/P0_25") (class "Default")
      (node (ref "U1") (pin "9") (pinfunction "P0.25/RD1_9") (pintype "passive"))
      (node (ref "U4") (pin "9") (pinfunction "C_9") (pintype "input"))
    )
    (net (code "62") (name "/P0_27") (class "Default")
      (node (ref "U1") (pin "11") (pinfunction "P0.27/AIN0/CAP0.1/MAT0.1_11") (pintype "passive"))
      (node (ref "U7") (pin "2") (pinfunction "inA_2") (pintype "passive"))
    )
    (net (code "63") (name "/P0_28") (class "Default")
      (node (ref "R97") (pin "1") (pinfunction "1_1") (pintype "passive"))
      (node (ref "U1") (pin "13") (pinfunction "P0.28/AIN1/CAP0.2/MAT0.2_13") (pintype "passive"))
      (node (ref "U24") (pin "5") (pinfunction "~{RESET}_5") (pintype "passive"))
    )
    (net (code "64") (name "/P0_29") (class "Default")
      (node (ref "U1") (pin "14") (pinfunction "P0.29/AIN2/CAP0.3/MAT0.3_14") (pintype "passive"))
      (node (ref "U7") (pin "4") (pinfunction "inB_4") (pintype "passive"))
    )
    (net (code "65") (name "/P0_30") (class "Default")
      (node (ref "U1") (pin "15") (pinfunction "P0.30/AIN3/EINT3/CAP0.0_15") (pintype "passive"))
      (node (ref "U4") (pin "3") (pinfunction "X_3") (pintype "bidirectional"))
    )
    (net (code "66") (name "/P1_16") (class "Default")
      (node (ref "JP2") (pin "2") (pinfunction "2_2") (pintype "passive"))
      (node (ref "U1") (pin "16") (pinfunction "P1.16/TRACEPKT0_16") (pintype "passive"))
    )
    (net (code "67") (name "/P1_17") (class "Default")
      (node (ref "JP2") (pin "3") (pinfunction "3_3") (pintype "passive"))
      (node (ref "U1") (pin "12") (pinfunction "P1.17/TRACEPKT1_12") (pintype "passive"))
    )
    (net (code "68") (name "/P1_18") (class "Default")
      (node (ref "JP2") (pin "4") (pinfunction "4_4") (pintype "passive"))
      (node (ref "U1") (pin "8") (pinfunction "P1.18/TRACEPKT2_8") (pintype "passive"))
    )
    (net (code "69") (name "/P1_19") (class "Default")
      (node (ref "JP2") (pin "5") (pinfunction "5_5") (pintype "passive"))
      (node (ref "U1") (pin "4") (pinfunction "P1.19/TRACEPKT3_4") (pintype "passive"))
    )
    (net (code "70") (name "/P1_20") (class "Default")
      (node (ref "JP2") (pin "1") (pinfunction "1_1") (pintype "passive"))
      (node (ref "U1") (pin "48") (pinfunction "P1.20/TRACESYNC_48") (pintype "passive"))
    )
    (net (code "71") (name "/P1_21") (class "Default")
      (node (ref "U1") (pin "44") (pinfunction "P1.21/PIPESTAT0_44") (pintype "passive"))
    )
    (net (code "72") (name "/P1_22") (class "Default")
      (node (ref "R14") (pin "1") (pinfunction "1_1") (pintype "passive"))
      (node (ref "U1") (pin "40") (pinfunction "P1.22/PIPESTAT1_40") (pintype "passive"))
    )
    (net (code "73") (name "/P1_23") (class "Default")
      (node (ref "U1") (pin "36") (pinfunction "P1.23/PIPESTAT2_36") (pintype "passive"))
      (node (ref "U2") (pin "6") (pinfunction "E2_6") (pintype "passive"))
    )
    (net (code "74") (name "/P1_24") (class "Default")
      (node (ref "U1") (pin "32") (pinfunction "P1.24/TRACECLK_32") (pintype "passive"))
    )
    (net (code "75") (name "/P1_25") (class "Default")
      (node (ref "U1") (pin "28") (pinfunction "P1.25/EXTIN0_28") (pintype "passive"))
    )
    (net (code "76") (name "/P1_26") (class "Default")
      (node (ref "U1") (pin "24") (pinfunction "P1.26/RTCK_24") (pintype "passive"))
    )
    (net (code "77") (name "/P1_27") (class "Default")
      (node (ref "R34") (pin "1") (pinfunction "1_1") (pintype "passive"))
      (node (ref "U1") (pin "64") (pinfunction "P1.27/TD0_64") (pintype "passive"))
    )
    (net (code "78") (name "/P1_28") (class "Default")
      (node (ref "U1") (pin "60") (pinfunction "P1.28/TDI_60") (pintype "passive"))
    )
    (net (code "79") (name "/P1_29") (class "Default")
      (node (ref "U1") (pin "56") (pinfunction "P1.29/TCK_56") (pintype "passive"))
    )
    (net (code "80") (name "/P1_30") (class "Default")
      (node (ref "U1") (pin "52") (pinfunction "P1.30/TMS_52") (pintype "passive"))
      (node (ref "U2") (pin "4") (pinfunction "A0_4") (pintype "passive"))
    )
    (net (code "81") (name "/P1_31") (class "Default")
      (node (ref "U1") (pin "20") (pinfunction "P1.31/~{TRST}_20") (pintype "passive"))
    )
    (net (code "82") (name "/PWM1") (class "Default")
      (node (ref "JP1") (pin "22") (pinfunction "22_22") (pintype "passive"))
      (node (ref "R40") (pin "1") (pinfunction "1_1") (pintype "passive"))
    )
    (net (code "83") (name "/PWM2") (class "Default")
      (node (ref "JP1") (pin "16") (pinfunction "16_16") (pintype "passive"))
      (node (ref "R41") (pin "1") (pinfunction "1_1") (pintype "passive"))
    )
    (net (code "84") (name "/RES") (class "Default")
      (node (ref "U1") (pin "57") (pinfunction "~{RESET}_57") (pintype "passive"))
      (node (ref "X34") (pin "1") (pinfunction "1_1") (pintype "passive"))
    )
    (net (code "85") (name "/RX0") (class "Default")
      (node (ref "JP10") (pin "3") (pinfunction "3_3") (pintype "passive"))
    )
    (net (code "86") (name "/Ref") (class "Default")
      (node (ref "C22") (pin "1") (pinfunction "1_1") (pintype "passive"))
      (node (ref "U10") (pin "6") (pinfunction "OUT_6") (pintype "power_in"))
      (node (ref "U24") (pin "9") (pinfunction "REF_IN(+)_9") (pintype "passive"))
    )
    (net (code "87") (name "/TD1") (class "Default")
      (node (ref "U1") (pin "10") (pinfunction "TD1_10") (pintype "passive"))
    )
    (net (code "88") (name "/TX0") (class "Default")
      (node (ref "JP6") (pin "12") (pinfunction "12_12") (pintype "passive"))
      (node (ref "X45") (pin "1") (pinfunction "1_1") (pintype "passive"))
    )
    (net (code "89") (name "/prog0") (class "Default")
      (node (ref "X29") (pin "1") (pinfunction "1_1") (pintype "passive"))
    )
    (net (code "90") (name "/prog1") (class "Default")
      (node (ref "X37") (pin "1") (pinfunction "1_1") (pintype "passive"))
    )
    (net (code "91") (name "GND") (class "Default")
      (node (ref "C1") (pin "2") (pinfunction "2_2") (pintype "passive"))
      (node (ref "C10") (pin "2") (pinfunction "2_2") (pintype "passive"))
      (node (ref "C11") (pin "1") (pinfunction "1_1") (pintype "passive"))
      (node (ref "C14") (pin "1") (pinfunction "1_1") (pintype "passive"))
      (node (ref "C15") (pin "1") (pinfunction "1_1") (pintype "passive"))
      (node (ref "C16") (pin "1") (pinfunction "1_1") (pintype "passive"))
      (node (ref "C17") (pin "1") (pinfunction "1_1") (pintype "passive"))
      (node (ref "C19") (pin "2") (pinfunction "2_2") (pintype "passive"))
      (node (ref "C20") (pin "2") (pinfunction "2_2") (pintype "passive"))
      (node (ref "C21") (pin "1") (pinfunction "1_1") (pintype "passive"))
      (node (ref "C22") (pin "2") (pinfunction "2_2") (pintype "passive"))
      (node (ref "C23") (pin "1") (pinfunction "1_1") (pintype "passive"))
      (node (ref "C24") (pin "1") (pinfunction "1_1") (pintype "passive"))
      (node (ref "C31") (pin "1") (pinfunction "1_1") (pintype "passive"))
      (node (ref "C32") (pin "1") (pinfunction "1_1") (pintype "passive"))
      (node (ref "C33") (pin "1") (pinfunction "1_1") (pintype "passive"))
      (node (ref "C4") (pin "1") (pinfunction "1_1") (pintype "passive"))
      (node (ref "C50") (pin "1") (pinfunction "1_1") (pintype "passive"))
      (node (ref "C53") (pin "1") (pinfunction "1_1") (pintype "passive"))
      (node (ref "C54") (pin "1") (pinfunction "1_1") (pintype "passive"))
      (node (ref "D9") (pin "1") (pinfunction "A_1") (pintype "passive"))
      (node (ref "JP1") (pin "12") (pinfunction "12_12") (pintype "passive"))
      (node (ref "JP1") (pin "26") (pinfunction "26_26") (pintype "passive"))
      (node (ref "JP1") (pin "3") (pinfunction "3_3") (pintype "passive"))
      (node (ref "JP4") (pin "1") (pinfunction "1_1") (pintype "passive"))
      (node (ref "JP6") (pin "15") (pinfunction "15_15") (pintype "passive"))
      (node (ref "JP6") (pin "16") (pinfunction "16_16") (pintype "passive"))
      (node (ref "Q1") (pin "2") (pinfunction "E_2") (pintype "passive"))
      (node (ref "Q3") (pin "2") (pinfunction "E_2") (pintype "passive"))
      (node (ref "R36") (pin "1") (pinfunction "1_1") (pintype "passive"))
      (node (ref "R57") (pin "1") (pinfunction "1_1") (pintype "passive"))
      (node (ref "R6") (pin "2") (pinfunction "2_2") (pintype "passive"))
      (node (ref "R65") (pin "1") (pinfunction "1_1") (pintype "passive"))
      (node (ref "U1") (pin "18") (pinfunction "Vss_18") (pintype "passive"))
      (node (ref "U1") (pin "25") (pinfunction "Vss_25") (pintype "passive"))
      (node (ref "U1") (pin "42") (pinfunction "Vss_42") (pintype "passive"))
      (node (ref "U1") (pin "50") (pinfunction "Vss_50") (pintype "passive"))
      (node (ref "U1") (pin "58") (pinfunction "VssA_PLL_58") (pintype "passive"))
      (node (ref "U1") (pin "59") (pinfunction "VssA_59") (pintype "passive"))
      (node (ref "U1") (pin "6") (pinfunction "Vss_6") (pintype "passive"))
      (node (ref "U10") (pin "4") (pinfunction "GND_4") (pintype "power_in"))
      (node (ref "U19") (pin "2") (pinfunction "GND_2") (pintype "power_in"))
      (node (ref "U2") (pin "1") (pinfunction "GND_1") (pintype "passive"))
      (node (ref "U2") (pin "20") (pinfunction "BL-_20") (pintype "passive"))
      (node (ref "U20") (pin "2") (pinfunction "GND_2") (pintype "power_in"))
      (node (ref "U24") (pin "10") (pinfunction "REF_IN(-)_10") (pintype "passive"))
      (node (ref "U24") (pin "16") (pinfunction "GND_16") (pintype "passive"))
      (node (ref "U4") (pin "6") (pinfunction "INH_6") (pintype "input"))
      (node (ref "U4") (pin "7") (pinfunction "VEE_7") (pintype "power_in"))
      (node (ref "U4") (pin "8") (pinfunction "VSS_8") (pintype "power_in"))
      (node (ref "U7") (pin "3") (pinfunction "GND_3") (pintype "passive"))
    )
    (net (code "92") (name "Net-(A1-Pad2)") (class "Default")
      (node (ref "A1") (pin "2") (pinfunction "2_2") (pintype "passive"))
      (node (ref "C19") (pin "1") (pinfunction "1_1") (pintype "passive"))
      (node (ref "R56") (pin "1") (pinfunction "1_1") (pintype "passive"))
      (node (ref "R57") (pin "2") (pinfunction "2_2") (pintype "passive"))
    )
    (net (code "93") (name "Net-(C34-Pad2)") (class "Default")
      (node (ref "C34") (pin "2") (pinfunction "2_2") (pintype "passive"))
      (node (ref "C36") (pin "2") (pinfunction "2_2") (pintype "passive"))
      (node (ref "R46") (pin "2") (pinfunction "2_2") (pintype "passive"))
      (node (ref "R81") (pin "1") (pinfunction "1_1") (pintype "passive"))
      (node (ref "R82") (pin "1") (pinfunction "1_1") (pintype "passive"))
      (node (ref "X39") (pin "1") (pinfunction "1_1") (pintype "passive"))
      (node (ref "X40") (pin "1") (pinfunction "1_1") (pintype "passive"))
    )
    (net (code "94") (name "Net-(D2-A)") (class "Default")
      (node (ref "C34") (pin "1") (pinfunction "1_1") (pintype "passive"))
      (node (ref "D2") (pin "1") (pinfunction "A_1") (pintype "passive"))
      (node (ref "JP5") (pin "1") (pinfunction "1_1") (pintype "passive"))
      (node (ref "Q11") (pin "2") (pinfunction "E_2") (pintype "passive"))
      (node (ref "R79") (pin "1") (pinfunction "1_1") (pintype "passive"))
      (node (ref "S1") (pin "1") (pinfunction "1_1") (pintype "passive"))
      (node (ref "S2") (pin "1") (pinfunction "1_1") (pintype "passive"))
      (node (ref "S3") (pin "1") (pinfunction "1_1") (pintype "passive"))
      (node (ref "S4") (pin "1") (pinfunction "1_1") (pintype "passive"))
      (node (ref "S5") (pin "1") (pinfunction "1_1") (pintype "passive"))
    )
    (net (code "95") (name "Net-(D2-K)") (class "Default")
      (node (ref "C36") (pin "1") (pinfunction "1_1") (pintype "passive"))
      (node (ref "D2") (pin "2") (pinfunction "K_2") (pintype "passive"))
      (node (ref "R80") (pin "2") (pinfunction "2_2") (pintype "passive"))
    )
    (net (code "96") (name "Net-(JP3-Pad1)") (class "Default")
      (node (ref "JP3") (pin "1") (pinfunction "1_1") (pintype "passive"))
      (node (ref "R1") (pin "2") (pinfunction "2_2") (pintype "passive"))
    )
    (net (code "97") (name "Net-(JP3-Pad2)") (class "Default")
      (node (ref "JP3") (pin "2") (pinfunction "2_2") (pintype "passive"))
      (node (ref "R2") (pin "2") (pinfunction "2_2") (pintype "passive"))
    )
    (net (code "98") (name "Net-(JP3-Pad3)") (class "Default")
      (node (ref "JP3") (pin "3") (pinfunction "3_3") (pintype "passive"))
      (node (ref "R3") (pin "2") (pinfunction "2_2") (pintype "passive"))
    )
    (net (code "99") (name "Net-(JP3-Pad4)") (class "Default")
      (node (ref "JP3") (pin "4") (pinfunction "4_4") (pintype "passive"))
      (node (ref "R4") (pin "2") (pinfunction "2_2") (pintype "passive"))
    )
    (net (code "100") (name "Net-(JP3-Pad5)") (class "Default")
      (node (ref "JP3") (pin "5") (pinfunction "5_5") (pintype "passive"))
      (node (ref "R5") (pin "2") (pinfunction "2_2") (pintype "passive"))
    )
    (net (code "101") (name "Net-(JP5-Pad2)") (class "Default")
      (node (ref "JP5") (pin "2") (pinfunction "2_2") (pintype "passive"))
      (node (ref "X47") (pin "1") (pinfunction "1_1") (pintype "passive"))
    )
    (net (code "102") (name "Net-(JP5-Pad3)") (class "Default")
      (node (ref "JP5") (pin "3") (pinfunction "3_3") (pintype "passive"))
      (node (ref "X31") (pin "1") (pinfunction "1_1") (pintype "passive"))
    )
    (net (code "103") (name "Net-(JP10-Pad1)") (class "Default")
      (node (ref "JP10") (pin "1") (pinfunction "1_1") (pintype "passive"))
      (node (ref "JP6") (pin "11") (pinfunction "11_11") (pintype "passive"))
    )
    (net (code "104") (name "Net-(JP10-Pad2)") (class "Default")
      (node (ref "JP10") (pin "2") (pinfunction "2_2") (pintype "passive"))
      (node (ref "X25") (pin "1") (pinfunction "1_1") (pintype "passive"))
    )
    (net (code "105") (name "Net-(Q1-B)") (class "Default")
      (node (ref "Q1") (pin "1") (pinfunction "B_1") (pintype "passive"))
      (node (ref "R34") (pin "2") (pinfunction "2_2") (pintype "passive"))
      (node (ref "R36") (pin "2") (pinfunction "2_2") (pintype "passive"))
    )
    (net (code "106") (name "Net-(Q1-C)") (class "Default")
      (node (ref "A1") (pin "1") (pinfunction "1_1") (pintype "passive"))
      (node (ref "Q1") (pin "3") (pinfunction "C_3") (pintype "passive"))
    )
    (net (code "107") (name "Net-(Q2-B)") (class "Default")
      (node (ref "Q2") (pin "1") (pinfunction "B_1") (pintype "passive"))
      (node (ref "R10") (pin "2") (pinfunction "2_2") (pintype "passive"))
    )
    (net (code "108") (name "Net-(Q2-C)") (class "Default")
      (node (ref "Q2") (pin "3") (pinfunction "C_3") (pintype "passive"))
      (node (ref "U2") (pin "2") (pinfunction "GND_2") (pintype "passive"))
    )
    (net (code "109") (name "Net-(Q3-B)") (class "Default")
      (node (ref "Q3") (pin "1") (pinfunction "B_1") (pintype "passive"))
      (node (ref "R14") (pin "2") (pinfunction "2_2") (pintype "passive"))
    )
    (net (code "110") (name "Net-(Q3-C)") (class "Default")
      (node (ref "Q3") (pin "3") (pinfunction "C_3") (pintype "passive"))
      (node (ref "R10") (pin "1") (pinfunction "1_1") (pintype "passive"))
    )
    (net (code "111") (name "Net-(Q4-B)") (class "Default")
      (node (ref "Q4") (pin "1") (pinfunction "B_1") (pintype "passive"))
      (node (ref "R89") (pin "1") (pinfunction "1_1") (pintype "passive"))
      (node (ref "R90") (pin "2") (pinfunction "2_2") (pintype "passive"))
    )
    (net (code "112") (name "Net-(Q4-E)") (class "Default")
      (node (ref "Q4") (pin "2") (pinfunction "E_2") (pintype "passive"))
      (node (ref "U2") (pin "3") (pinfunction "V0_3") (pintype "passive"))
    )
    (net (code "113") (name "Net-(Q11-B)") (class "Default")
      (node (ref "Q11") (pin "1") (pinfunction "B_1") (pintype "passive"))
      (node (ref "R79") (pin "2") (pinfunction "2_2") (pintype "passive"))
      (node (ref "R80") (pin "1") (pinfunction "1_1") (pintype "passive"))
    )
    (net (code "114") (name "Net-(Q11-C)") (class "Default")
      (node (ref "Q11") (pin "3") (pinfunction "C_3") (pintype "passive"))
      (node (ref "R81") (pin "2") (pinfunction "2_2") (pintype "passive"))
      (node (ref "X35") (pin "1") (pinfunction "1_1") (pintype "passive"))
      (node (ref "X36") (pin "1") (pinfunction "1_1") (pintype "passive"))
    )
    (net (code "115") (name "Net-(R1-Pad1)") (class "Default")
      (node (ref "R1") (pin "1") (pinfunction "1_1") (pintype "passive"))
      (node (ref "S1") (pin "2") (pinfunction "2_2") (pintype "passive"))
    )
    (net (code "116") (name "Net-(R2-Pad1)") (class "Default")
      (node (ref "R2") (pin "1") (pinfunction "1_1") (pintype "passive"))
      (node (ref "S2") (pin "2") (pinfunction "2_2") (pintype "passive"))
    )
    (net (code "117") (name "Net-(R3-Pad1)") (class "Default")
      (node (ref "R3") (pin "1") (pinfunction "1_1") (pintype "passive"))
      (node (ref "S3") (pin "2") (pinfunction "2_2") (pintype "passive"))
    )
    (net (code "118") (name "Net-(R4-Pad1)") (class "Default")
      (node (ref "R4") (pin "1") (pinfunction "1_1") (pintype "passive"))
      (node (ref "S4") (pin "2") (pinfunction "2_2") (pintype "passive"))
    )
    (net (code "119") (name "Net-(R5-Pad1)") (class "Default")
      (node (ref "R5") (pin "1") (pinfunction "1_1") (pintype "passive"))
      (node (ref "S5") (pin "2") (pinfunction "2_2") (pintype "passive"))
    )
    (net (code "120") (name "Net-(R43-Pad1)") (class "Default")
      (node (ref "R43") (pin "1") (pinfunction "1_1") (pintype "passive"))
      (node (ref "X43") (pin "1") (pinfunction "1_1") (pintype "passive"))
    )
    (net (code "121") (name "Net-(R43-Pad2)") (class "Default")
      (node (ref "R43") (pin "2") (pinfunction "2_2") (pintype "passive"))
      (node (ref "X44") (pin "1") (pinfunction "1_1") (pintype "passive"))
    )
    (net (code "122") (name "Net-(R46-Pad1)") (class "Default")
      (node (ref "R46") (pin "1") (pinfunction "1_1") (pintype "passive"))
      (node (ref "X23") (pin "1") (pinfunction "1_1") (pintype "passive"))
      (node (ref "X24") (pin "1") (pinfunction "1_1") (pintype "passive"))
    )
    (net (code "123") (name "Net-(R82-Pad2)") (class "Default")
      (node (ref "R82") (pin "2") (pinfunction "2_2") (pintype "passive"))
      (node (ref "X27") (pin "1") (pinfunction "1_1") (pintype "passive"))
      (node (ref "X28") (pin "1") (pinfunction "1_1") (pintype "passive"))
    )
    (net (code "124") (name "Net-(U1-XTAL1)") (class "Default")
      (node (ref "C21") (pin "2") (pinfunction "2_2") (pintype "passive"))
      (node (ref "U1") (pin "61") (pinfunction "XTAL1_61") (pintype "passive"))
      (node (ref "Y1") (pin "1") (pinfunction "OSC1_1") (pintype "passive"))
    )
    (net (code "125") (name "Net-(U1-XTAL2)") (class "Default")
      (node (ref "C31") (pin "2") (pinfunction "2_2") (pintype "passive"))
      (node (ref "U1") (pin "62") (pinfunction "XTAL2_62") (pintype "passive"))
      (node (ref "Y1") (pin "2") (pinfunction "OSC2_2") (pintype "passive"))
    )
    (net (code "126") (name "Net-(U2-DB2)") (class "Default")
      (node (ref "R35") (pin "2") (pinfunction "2_2") (pintype "passive"))
      (node (ref "U2") (pin "12") (pinfunction "DB2_12") (pintype "passive"))
    )
    (net (code "127") (name "Net-(U7-outA)") (class "Default")
      (node (ref "R40") (pin "2") (pinfunction "2_2") (pintype "passive"))
      (node (ref "U7") (pin "7") (pinfunction "outA_7") (pintype "passive"))
    )
    (net (code "128") (name "Net-(U7-outB)") (class "Default")
      (node (ref "R41") (pin "2") (pinfunction "2_2") (pintype "passive"))
      (node (ref "U7") (pin "5") (pinfunction "outB_5") (pintype "passive"))
    )
    (net (code "129") (name "Net-(U24-AIN1(-))") (class "Default")
      (node (ref "C23") (pin "2") (pinfunction "2_2") (pintype "passive"))
      (node (ref "R15") (pin "1") (pinfunction "1_1") (pintype "passive"))
      (node (ref "U24") (pin "8") (pinfunction "AIN1(-)_8") (pintype "passive"))
    )
    (net (code "130") (name "Net-(U24-AIN2(-))") (class "Default")
      (node (ref "C4") (pin "2") (pinfunction "2_2") (pintype "passive"))
      (node (ref "R18") (pin "1") (pinfunction "1_1") (pintype "passive"))
      (node (ref "U24") (pin "11") (pinfunction "AIN2(-)_11") (pintype "passive"))
    )
    (net (code "131") (name "Net-(U24-MCLK_IN)") (class "Default")
      (node (ref "C50") (pin "2") (pinfunction "2_2") (pintype "passive"))
      (node (ref "U24") (pin "2") (pinfunction "MCLK_IN_2") (pintype "passive"))
      (node (ref "Y3") (pin "1") (pinfunction "OSC1_1") (pintype "passive"))
    )
    (net (code "132") (name "Net-(U24-MCLK_OUT)") (class "Default")
      (node (ref "C53") (pin "2") (pinfunction "2_2") (pintype "passive"))
      (node (ref "U24") (pin "3") (pinfunction "MCLK_OUT_3") (pintype "passive"))
      (node (ref "Y3") (pin "2") (pinfunction "OSC2_2") (pintype "passive"))
    )
    (net (code "133") (name "unconnected-(JP1-Pad9)") (class "Default")
      (node (ref "JP1") (pin "9") (pinfunction "9_9") (pintype "passive"))
    )
    (net (code "134") (name "unconnected-(JP1-Pad14)") (class "Default")
      (node (ref "JP1") (pin "14") (pinfunction "14_14") (pintype "passive"))
    )
    (net (code "135") (name "unconnected-(JP1-Pad23)") (class "Default")
      (node (ref "JP1") (pin "23") (pinfunction "23_23") (pintype "passive"))
    )
    (net (code "136") (name "unconnected-(JP6-Pad9)") (class "Default")
      (node (ref "JP6") (pin "9") (pinfunction "9_9") (pintype "passive"))
    )
    (net (code "137") (name "unconnected-(JP6-Pad10)") (class "Default")
      (node (ref "JP6") (pin "10") (pinfunction "10_10") (pintype "passive"))
    )
    (net (code "138") (name "unconnected-(U4-X7-Pad4)") (class "Default")
      (node (ref "U4") (pin "4") (pinfunction "X7_4") (pintype "bidirectional"))
    )
    (net (code "139") (name "unconnected-(U10-NC-Pad7)") (class "Default")
      (node (ref "U10") (pin "7") (pinfunction "NC_7") (pintype "passive"))
    )
    (net (code "140") (name "unconnected-(U10-NC-Pad8)") (class "Default")
      (node (ref "U10") (pin "8") (pinfunction "NC_8") (pintype "passive"))
    )
    (net (code "141") (name "unconnected-(U10-SLE-Pad3)") (class "Default")
      (node (ref "U10") (pin "3") (pinfunction "SLE_3") (pintype "input"))
    )
    (net (code "142") (name "unconnected-(U10-TP-Pad1)") (class "Default")
      (node (ref "U10") (pin "1") (pinfunction "TP_1") (pintype "passive"))
    )
    (net (code "143") (name "unconnected-(U10-TP-Pad5)") (class "Default")
      (node (ref "U10") (pin "5") (pinfunction "TP_5") (pintype "passive"))
    )
    (net (code "144") (name "unconnected-(U19-NC-Pad4)") (class "Default")
      (node (ref "U19") (pin "4") (pinfunction "NC_4") (pintype "passive"))
    )
    (net (code "145") (name "unconnected-(U20-NC-Pad4)") (class "Default")
      (node (ref "U20") (pin "4") (pinfunction "NC_4") (pintype "passive"))
    )
    (net (code "146") (name "unconnected-(U24-~{DRDY}-Pad12)") (class "Default")
      (node (ref "U24") (pin "12") (pinfunction "~{DRDY}_12") (pintype "passive"))
    )
    (net (code "147") (name "unconnected-(X32-Pad1)") (class "Default")
      (node (ref "X32") (pin "1") (pinfunction "1_1") (pintype "passive"))
    )
    (net (code "148") (name "unconnected-(X33-Pad1)") (class "Default")
      (node (ref "X33") (pin "1") (pinfunction "1_1") (pintype "passive"))
    )
  )
)
